# First_Sheet.net
KiCad netlist of a schematic drawn in Altium Designer
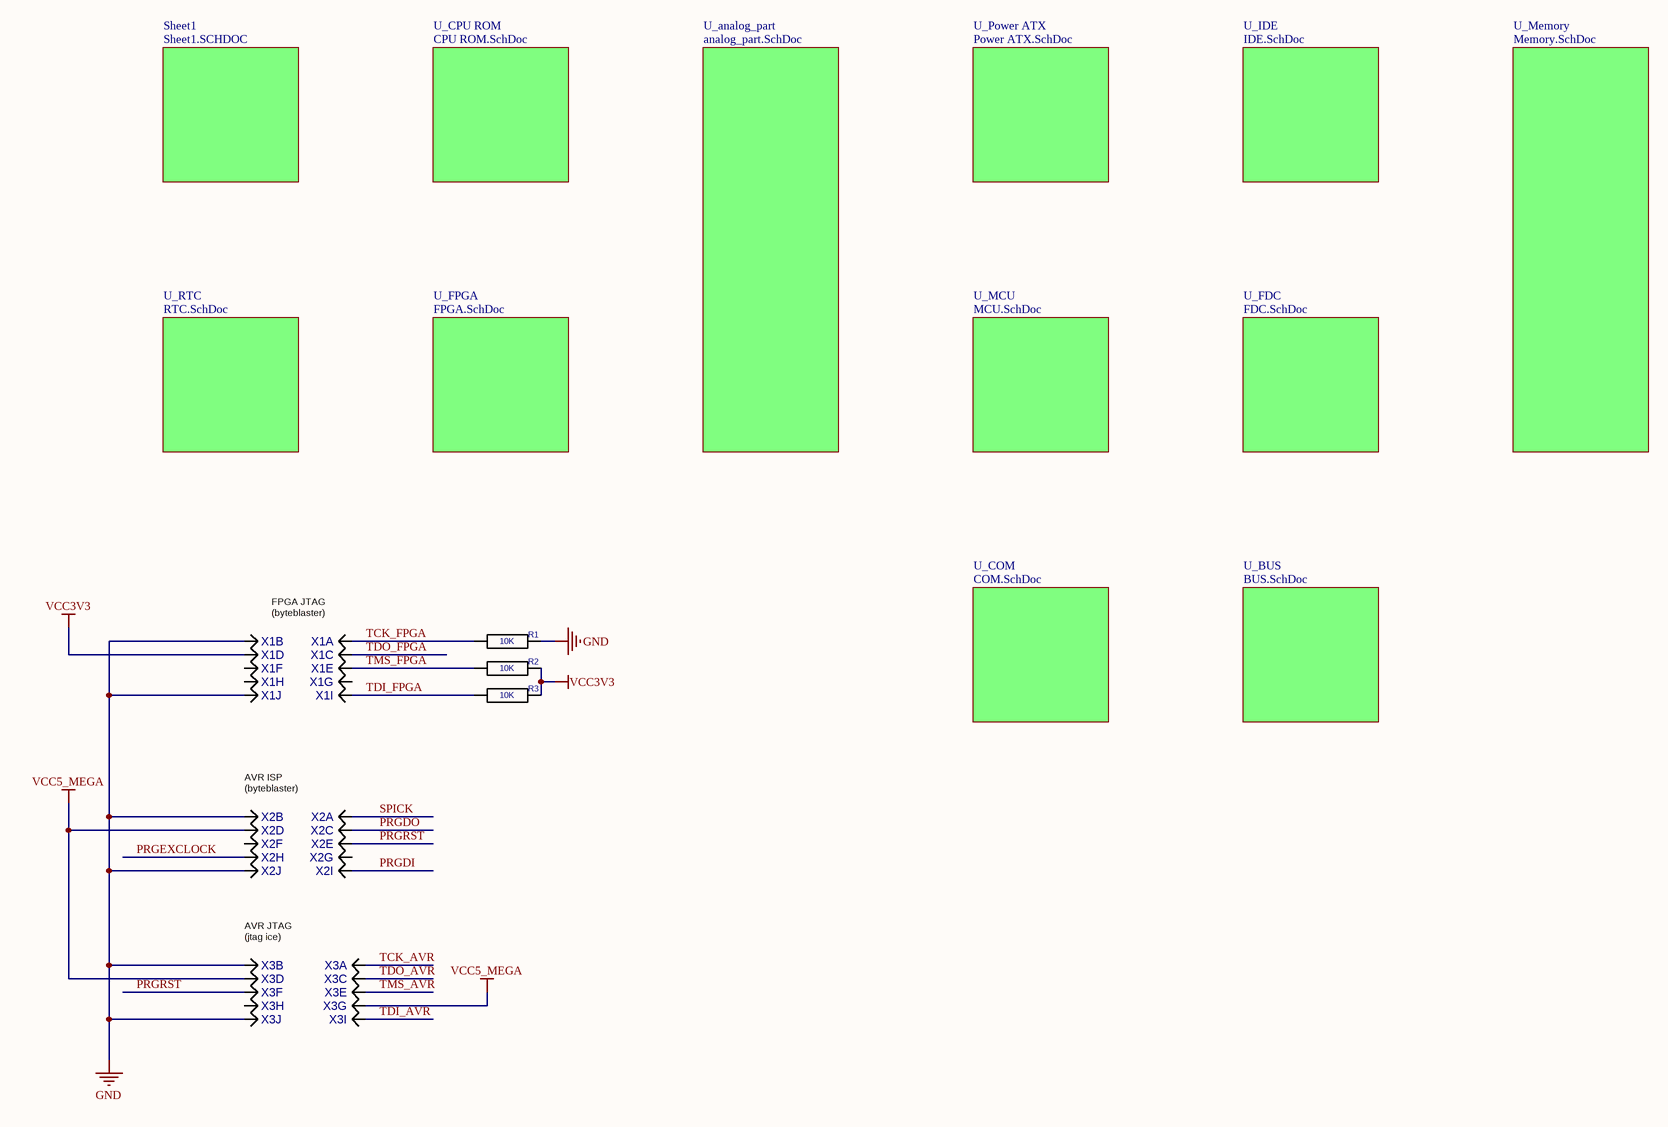
[diagram p0: First_Sheet.SCHDOC]

(export (version "E")
  (design (tool "Eeschema 10.0.6"))
  (components
    (comp (ref "R1")
      (value "10K")
      (footprint "R-CHIP")
      (description "RESCHIP")
      (libsource (lib "*") (part "RESCHIP"))
    )
    (comp (ref "R2")
      (value "10K")
      (footprint "R-CHIP")
      (description "RESCHIP")
      (libsource (lib "*") (part "RESCHIP"))
    )
    (comp (ref "R3")
      (value "10K")
      (footprint "R-CHIP")
      (description "RESCHIP")
      (libsource (lib "*") (part "RESCHIP"))
    )
    (comp (ref "X1") (value "IDC10M") (footprint "IDC10M") (libsource (lib "*") (part "IDC10M")))
    (comp (ref "X2") (value "IDC10M") (footprint "IDC10M") (libsource (lib "*") (part "IDC10M")))
    (comp (ref "X3") (value "IDC10M") (footprint "IDC10M") (libsource (lib "*") (part "IDC10M")))
  )
  (nets
    (net (code "1") (name "/PRGDI") (class "Default") (node (ref "X2") (pin "9") (pintype "passive")))
    (net (code "2") (name "/PRGDO") (class "Default") (node (ref "X2") (pin "3") (pintype "passive")))
    (net (code "3") (name "/PRGEXCLOCK") (class "Default") (node (ref "X2") (pin "8") (pintype "passive")))
    (net (code "4") (name "/SPICK") (class "Default") (node (ref "X2") (pin "1") (pintype "passive")))
    (net (code "5") (name "/TCK_AVR") (class "Default") (node (ref "X3") (pin "1") (pintype "passive")))
    (net (code "6") (name "/TCK_FPGA") (class "Default")
      (node (ref "R1") (pin "1") (pinfunction "i/o_1") (pintype "passive"))
      (node (ref "X1") (pin "1") (pintype "passive"))
    )
    (net (code "7") (name "/TDI_AVR") (class "Default") (node (ref "X3") (pin "9") (pintype "passive")))
    (net (code "8") (name "/TDI_FPGA") (class "Default")
      (node (ref "R3") (pin "1") (pinfunction "i/o_1") (pintype "passive"))
      (node (ref "X1") (pin "9") (pintype "passive"))
    )
    (net (code "9") (name "/TDO_AVR") (class "Default") (node (ref "X3") (pin "3") (pintype "passive")))
    (net (code "10") (name "/TDO_FPGA") (class "Default") (node (ref "X1") (pin "3") (pintype "passive")))
    (net (code "11") (name "/TMS_AVR") (class "Default") (node (ref "X3") (pin "5") (pintype "passive")))
    (net (code "12") (name "/TMS_FPGA") (class "Default")
      (node (ref "R2") (pin "1") (pinfunction "i/o_1") (pintype "passive"))
      (node (ref "X1") (pin "5") (pintype "passive"))
    )
    (net (code "13") (name "/~{PRGRST}") (class "Default")
      (node (ref "X2") (pin "5") (pintype "passive"))
      (node (ref "X3") (pin "6") (pintype "passive"))
    )
    (net (code "14") (name "GND") (class "Default")
      (node (ref "R1") (pin "2") (pinfunction "i/o1_2") (pintype "passive"))
      (node (ref "X1") (pin "10") (pintype "passive"))
      (node (ref "X1") (pin "2") (pintype "passive"))
      (node (ref "X2") (pin "10") (pintype "passive"))
      (node (ref "X2") (pin "2") (pintype "passive"))
      (node (ref "X3") (pin "10") (pintype "passive"))
      (node (ref "X3") (pin "2") (pintype "passive"))
    )
    (net (code "15") (name "VCC3V3") (class "Default")
      (node (ref "R2") (pin "2") (pinfunction "i/o1_2") (pintype "passive"))
      (node (ref "R3") (pin "2") (pinfunction "i/o1_2") (pintype "passive"))
      (node (ref "X1") (pin "4") (pintype "passive"))
    )
    (net (code "16") (name "VCC5_MEGA") (class "Default")
      (node (ref "X2") (pin "4") (pintype "passive"))
      (node (ref "X3") (pin "4") (pintype "passive"))
      (node (ref "X3") (pin "7") (pintype "passive"))
    )
    (net (code "17") (name "unconnected-(X1-Pad6)") (class "Default")
      (node (ref "X1") (pin "6") (pintype "passive"))
    )
    (net (code "18") (name "unconnected-(X1-Pad7)") (class "Default")
      (node (ref "X1") (pin "7") (pintype "passive"))
    )
    (net (code "19") (name "unconnected-(X1-Pad8)") (class "Default")
      (node (ref "X1") (pin "8") (pintype "passive"))
    )
    (net (code "20") (name "unconnected-(X2-Pad6)") (class "Default")
      (node (ref "X2") (pin "6") (pintype "passive"))
    )
    (net (code "21") (name "unconnected-(X2-Pad7)") (class "Default")
      (node (ref "X2") (pin "7") (pintype "passive"))
    )
    (net (code "22") (name "unconnected-(X3-Pad8)") (class "Default")
      (node (ref "X3") (pin "8") (pintype "passive"))
    )
  )
)
